# powerBoard.net
KiCad netlist of a schematic drawn in EAGLE
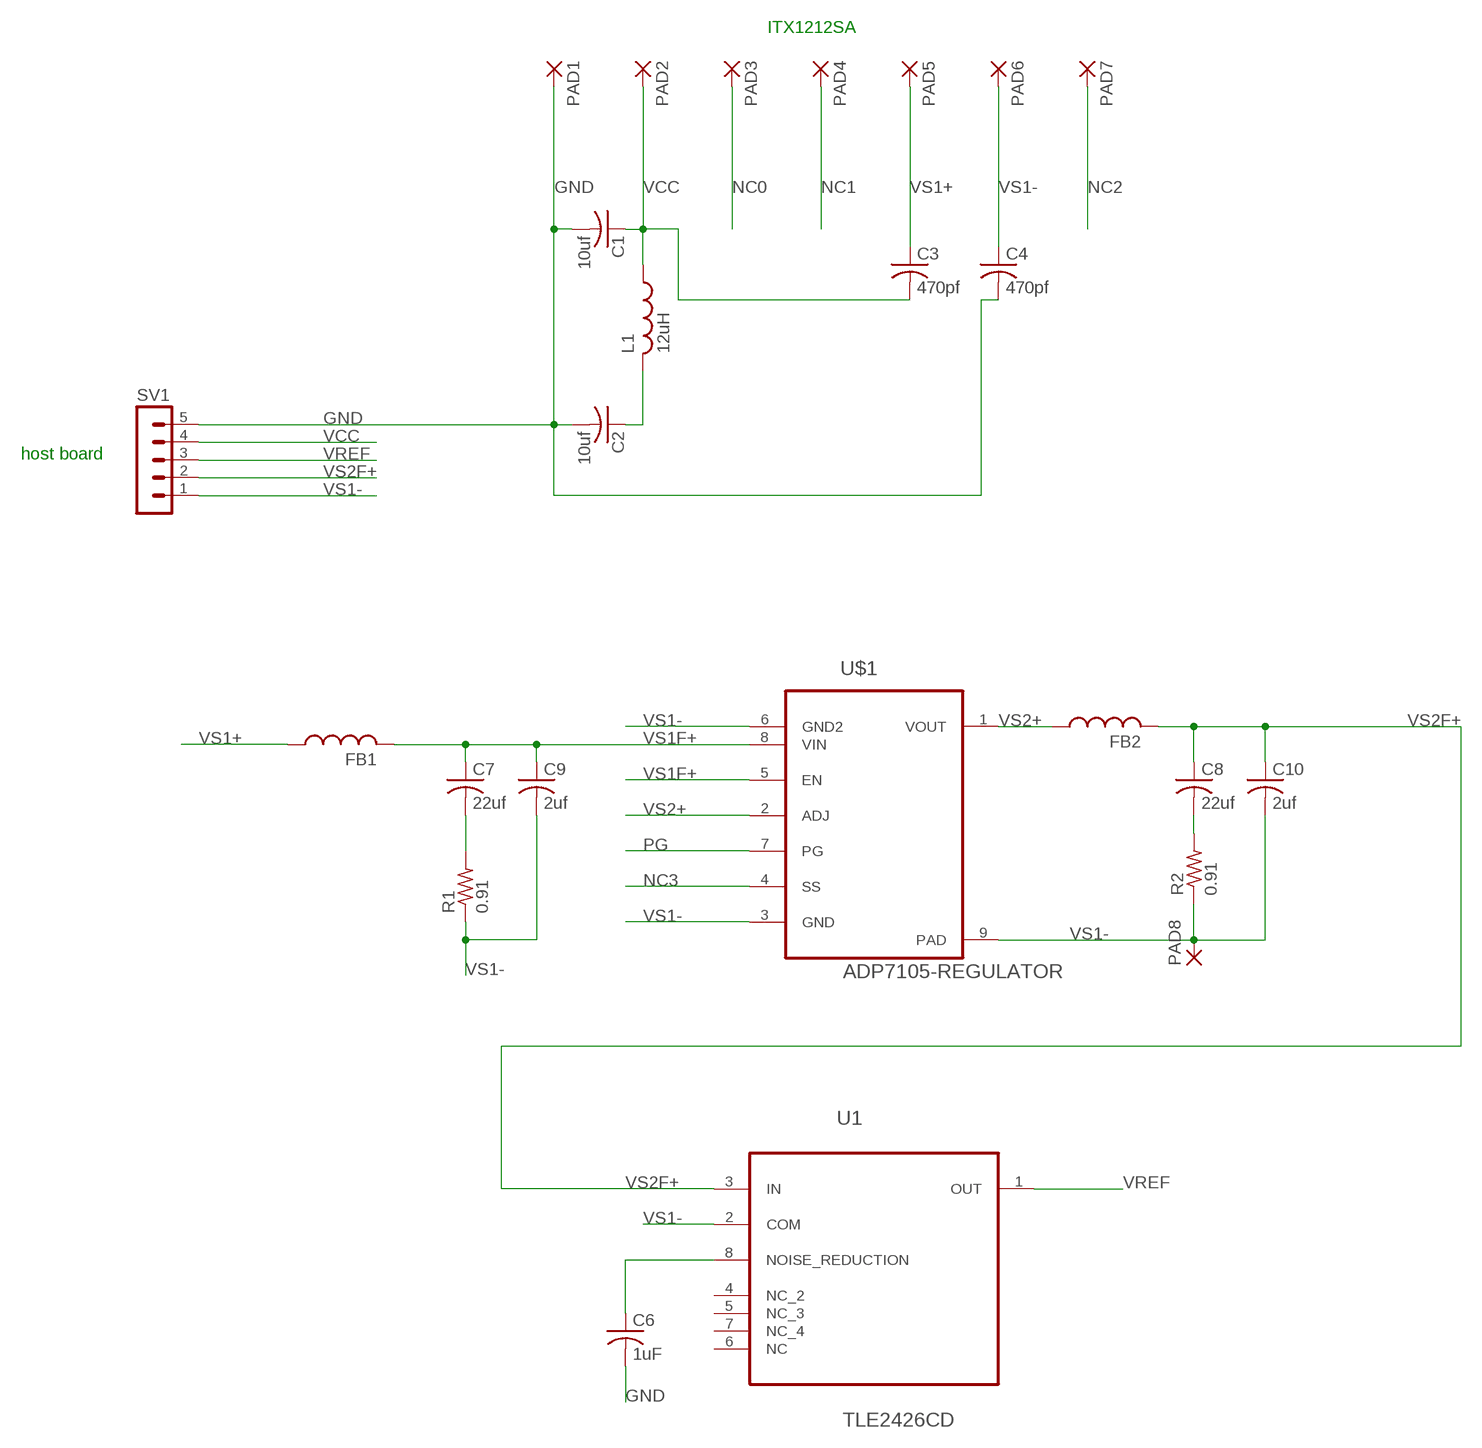
[diagram p0: schematic, sheet 1]

(export (version "E")
  (design (tool "Eeschema 10.0.6"))
  (components
    (comp (ref "C1")
      (value "10uf")
      (footprint "eagle-import:C0805K")
      (libsource (lib "eagle-import") (part "C-USC0805K"))
    )
    (comp (ref "C2")
      (value "10uf")
      (footprint "eagle-import:C0805K")
      (libsource (lib "eagle-import") (part "C-USC0805K"))
    )
    (comp (ref "C3")
      (value "470pf")
      (footprint "eagle-import:C0805K")
      (libsource (lib "eagle-import") (part "C-USC0805K"))
    )
    (comp (ref "C4")
      (value "470pf")
      (footprint "eagle-import:C0805K")
      (libsource (lib "eagle-import") (part "C-USC0805K"))
    )
    (comp (ref "C6")
      (value "1uF")
      (footprint "eagle-import:C0805")
      (libsource (lib "eagle-import") (part "C-USC0805"))
    )
    (comp (ref "C7")
      (value "22uf")
      (footprint "eagle-import:C0805K")
      (libsource (lib "eagle-import") (part "C-USC0805K"))
    )
    (comp (ref "C8")
      (value "22uf")
      (footprint "eagle-import:C0805K")
      (libsource (lib "eagle-import") (part "C-USC0805K"))
    )
    (comp (ref "C9")
      (value "2uf")
      (footprint "eagle-import:C0805K")
      (libsource (lib "eagle-import") (part "C-USC0805K"))
    )
    (comp (ref "C10")
      (value "2uf")
      (footprint "eagle-import:C0805K")
      (libsource (lib "eagle-import") (part "C-USC0805K"))
    )
    (comp (ref "FB1")
      (value "L-USL2012C")
      (footprint "eagle-import:L2012C")
      (libsource (lib "eagle-import") (part "L-USL2012C"))
    )
    (comp (ref "FB2")
      (value "L-USL2012C")
      (footprint "eagle-import:L2012C")
      (libsource (lib "eagle-import") (part "L-USL2012C"))
    )
    (comp (ref "L1")
      (value "12uH")
      (footprint "eagle-import:L2012C")
      (libsource (lib "eagle-import") (part "resistor_L-USL2012C"))
    )
    (comp (ref "PAD1")
      (value "SMD2")
      (footprint "eagle-import:SMD1,27-2,54")
      (libsource (lib "eagle-import") (part "SMD2"))
    )
    (comp (ref "PAD2")
      (value "SMD2")
      (footprint "eagle-import:SMD1,27-2,54")
      (libsource (lib "eagle-import") (part "SMD2"))
    )
    (comp (ref "PAD3")
      (value "SMD2")
      (footprint "eagle-import:SMD1,27-2,54")
      (libsource (lib "eagle-import") (part "SMD2"))
    )
    (comp (ref "PAD4")
      (value "SMD2")
      (footprint "eagle-import:SMD1,27-2,54")
      (libsource (lib "eagle-import") (part "SMD2"))
    )
    (comp (ref "PAD5")
      (value "SMD2")
      (footprint "eagle-import:SMD1,27-2,54")
      (libsource (lib "eagle-import") (part "SMD2"))
    )
    (comp (ref "PAD6")
      (value "SMD2")
      (footprint "eagle-import:SMD1,27-2,54")
      (libsource (lib "eagle-import") (part "SMD2"))
    )
    (comp (ref "PAD7")
      (value "SMD2")
      (footprint "eagle-import:SMD1,27-2,54")
      (libsource (lib "eagle-import") (part "SMD2"))
    )
    (comp (ref "PAD8")
      (value "2,54/1,1")
      (footprint "eagle-import:2,54_1,1")
      (libsource (lib "eagle-import") (part "2,54/1,1"))
    )
    (comp (ref "R1")
      (value "0.91")
      (footprint "eagle-import:R2012W")
      (libsource (lib "eagle-import") (part "R-US_R2012W"))
    )
    (comp (ref "R2")
      (value "0.91")
      (footprint "eagle-import:R2012W")
      (libsource (lib "eagle-import") (part "R-US_R2012W"))
    )
    (comp (ref "SV1")
      (value "MA05-1")
      (footprint "eagle-import:MA05-1")
      (libsource (lib "eagle-import") (part "MA05-1"))
    )
    (comp (ref "U$1")
      (value "ADP7105-REGULATOR")
      (footprint "eagle-import:ADP7105-REGULATOR")
      (libsource (lib "eagle-import") (part "ADP7105-REGULATOR"))
    )
    (comp (ref "U1")
      (value "TLE2426CD")
      (footprint "eagle-import:SOIC127P600X175-8N")
      (libsource (lib "eagle-import") (part "TLE2426CD"))
    )
  )
  (nets
    (net (code "1") (name "/GND") (class "Default")
      (node (ref "C1") (pin "2") (pinfunction "2_2") (pintype "passive"))
      (node (ref "C2") (pin "2") (pinfunction "2_2") (pintype "passive"))
      (node (ref "C4") (pin "2") (pinfunction "2_2") (pintype "passive"))
      (node (ref "C6") (pin "2") (pinfunction "2_2") (pintype "passive"))
      (node (ref "PAD1") (pin "1") (pinfunction "P_1") (pintype "passive"))
      (node (ref "SV1") (pin "5") (pinfunction "5_5") (pintype "passive"))
    )
    (net (code "2") (name "/NC0") (class "Default")
      (node (ref "PAD3") (pin "1") (pinfunction "P_1") (pintype "passive"))
    )
    (net (code "3") (name "/NC1") (class "Default")
      (node (ref "PAD4") (pin "1") (pinfunction "P_1") (pintype "passive"))
    )
    (net (code "4") (name "/NC2") (class "Default")
      (node (ref "PAD7") (pin "1") (pinfunction "P_1") (pintype "passive"))
    )
    (net (code "5") (name "/NC3") (class "Default")
      (node (ref "U$1") (pin "4") (pinfunction "SS_4") (pintype "passive"))
    )
    (net (code "7") (name "/PG") (class "Default")
      (node (ref "U$1") (pin "7") (pinfunction "PG_7") (pintype "no_connect"))
    )
    (net (code "8") (name "/VCC") (class "Default")
      (node (ref "C1") (pin "1") (pinfunction "1_1") (pintype "passive"))
      (node (ref "C3") (pin "2") (pinfunction "2_2") (pintype "passive"))
      (node (ref "L1") (pin "1") (pinfunction "1_1") (pintype "passive"))
      (node (ref "PAD2") (pin "1") (pinfunction "P_1") (pintype "passive"))
      (node (ref "SV1") (pin "4") (pinfunction "4_4") (pintype "passive"))
    )
    (net (code "9") (name "/VREF") (class "Default")
      (node (ref "SV1") (pin "3") (pinfunction "3_3") (pintype "passive"))
      (node (ref "U1") (pin "1") (pinfunction "OUT_1") (pintype "output"))
    )
    (net (code "10") (name "/VS1+") (class "Default")
      (node (ref "C3") (pin "1") (pinfunction "1_1") (pintype "passive"))
      (node (ref "FB1") (pin "1") (pinfunction "1_1") (pintype "passive"))
      (node (ref "PAD5") (pin "1") (pinfunction "P_1") (pintype "passive"))
    )
    (net (code "11") (name "/VS1-") (class "Default")
      (node (ref "C10") (pin "2") (pinfunction "2_2") (pintype "passive"))
      (node (ref "C4") (pin "1") (pinfunction "1_1") (pintype "passive"))
      (node (ref "C9") (pin "2") (pinfunction "2_2") (pintype "passive"))
      (node (ref "PAD6") (pin "1") (pinfunction "P_1") (pintype "passive"))
      (node (ref "PAD8") (pin "1") (pinfunction "P_1") (pintype "passive"))
      (node (ref "R1") (pin "1") (pinfunction "1_1") (pintype "passive"))
      (node (ref "R2") (pin "1") (pinfunction "1_1") (pintype "passive"))
      (node (ref "SV1") (pin "1") (pinfunction "1_1") (pintype "passive"))
      (node (ref "U$1") (pin "3") (pinfunction "GND_3") (pintype "passive"))
      (node (ref "U$1") (pin "6") (pinfunction "GND2_6") (pintype "power_in"))
      (node (ref "U$1") (pin "9") (pinfunction "PAD_9") (pintype "output"))
      (node (ref "U1") (pin "2") (pinfunction "COM_2") (pintype "passive"))
    )
    (net (code "12") (name "/VS1F+") (class "Default")
      (node (ref "C7") (pin "1") (pinfunction "1_1") (pintype "passive"))
      (node (ref "C9") (pin "1") (pinfunction "1_1") (pintype "passive"))
      (node (ref "FB1") (pin "2") (pinfunction "2_2") (pintype "passive"))
      (node (ref "U$1") (pin "5") (pinfunction "EN_5") (pintype "input"))
      (node (ref "U$1") (pin "8") (pinfunction "VIN_8") (pintype "power_in"))
    )
    (net (code "13") (name "/VS2+") (class "Default")
      (node (ref "FB2") (pin "1") (pinfunction "1_1") (pintype "passive"))
      (node (ref "U$1") (pin "1") (pinfunction "VOUT_1") (pintype "output"))
      (node (ref "U$1") (pin "2") (pinfunction "ADJ_2") (pintype "passive"))
    )
    (net (code "14") (name "/VS2F+") (class "Default")
      (node (ref "C10") (pin "1") (pinfunction "1_1") (pintype "passive"))
      (node (ref "C8") (pin "1") (pinfunction "1_1") (pintype "passive"))
      (node (ref "FB2") (pin "2") (pinfunction "2_2") (pintype "passive"))
      (node (ref "SV1") (pin "2") (pinfunction "2_2") (pintype "passive"))
      (node (ref "U1") (pin "3") (pinfunction "IN_3") (pintype "input"))
    )
    (net (code "15") (name "Net-(C2-Pad1)") (class "Default")
      (node (ref "C2") (pin "1") (pinfunction "1_1") (pintype "passive"))
      (node (ref "L1") (pin "2") (pinfunction "2_2") (pintype "passive"))
    )
    (net (code "16") (name "Net-(C7-Pad2)") (class "Default")
      (node (ref "C7") (pin "2") (pinfunction "2_2") (pintype "passive"))
      (node (ref "R1") (pin "2") (pinfunction "2_2") (pintype "passive"))
    )
    (net (code "17") (name "Net-(C8-Pad2)") (class "Default")
      (node (ref "C8") (pin "2") (pinfunction "2_2") (pintype "passive"))
      (node (ref "R2") (pin "2") (pinfunction "2_2") (pintype "passive"))
    )
    (net (code "18") (name "Net-(U1-NOISE_REDUCTION)") (class "Default")
      (node (ref "C6") (pin "1") (pinfunction "1_1") (pintype "passive"))
      (node (ref "U1") (pin "8") (pinfunction "NOISE_REDUCTION_8") (pintype "passive"))
    )
    (net (code "19") (name "unconnected-(U1-NC-Pad6)") (class "Default")
      (node (ref "U1") (pin "6") (pinfunction "NC_6") (pintype "no_connect"))
    )
    (net (code "20") (name "unconnected-(U1-NC_2-Pad4)") (class "Default")
      (node (ref "U1") (pin "4") (pinfunction "NC_2_4") (pintype "no_connect"))
    )
    (net (code "21") (name "unconnected-(U1-NC_3-Pad5)") (class "Default")
      (node (ref "U1") (pin "5") (pinfunction "NC_3_5") (pintype "no_connect"))
    )
    (net (code "22") (name "unconnected-(U1-NC_4-Pad7)") (class "Default")
      (node (ref "U1") (pin "7") (pinfunction "NC_4_7") (pintype "no_connect"))
    )
  )
)
